# ShematicPCB.net
KiCad netlist of a schematic drawn in EAGLE
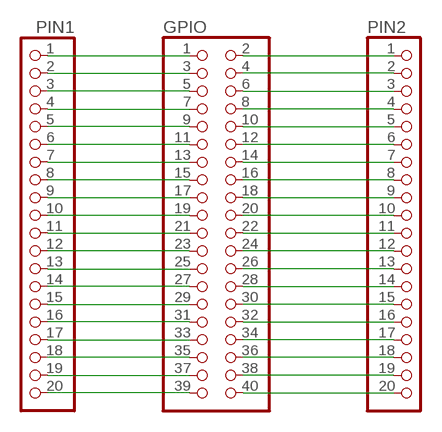
[diagram p0: schematic, sheet 1]

(export (version "E")
  (design (tool "Eeschema 10.0.6"))
  (components
    (comp (ref "GPIO")
      (value "PINHD-2X20")
      (footprint "eagle-import:2X20")
      (libsource (lib "eagle-import") (part "PINHD-2X20"))
    )
    (comp (ref "PIN1")
      (value "PINHD-1X20")
      (footprint "eagle-import:1X20")
      (libsource (lib "eagle-import") (part "PINHD-1X20"))
    )
    (comp (ref "PIN2")
      (value "PINHD-1X20")
      (footprint "eagle-import:1X20")
      (libsource (lib "eagle-import") (part "PINHD-1X20"))
    )
  )
  (nets
    (net (code "1") (name "Net-(GPIO-Pad1)") (class "Default")
      (node (ref "GPIO") (pin "1") (pinfunction "1_1") (pintype "passive"))
      (node (ref "PIN1") (pin "1") (pinfunction "1_1") (pintype "passive"))
    )
    (net (code "2") (name "Net-(GPIO-Pad2)") (class "Default")
      (node (ref "GPIO") (pin "2") (pinfunction "2_2") (pintype "passive"))
      (node (ref "PIN2") (pin "1") (pinfunction "1_1") (pintype "passive"))
    )
    (net (code "3") (name "Net-(GPIO-Pad3)") (class "Default")
      (node (ref "GPIO") (pin "3") (pinfunction "3_3") (pintype "passive"))
      (node (ref "PIN1") (pin "2") (pinfunction "2_2") (pintype "passive"))
    )
    (net (code "4") (name "Net-(GPIO-Pad4)") (class "Default")
      (node (ref "GPIO") (pin "4") (pinfunction "4_4") (pintype "passive"))
      (node (ref "PIN2") (pin "2") (pinfunction "2_2") (pintype "passive"))
    )
    (net (code "5") (name "Net-(GPIO-Pad5)") (class "Default")
      (node (ref "GPIO") (pin "5") (pinfunction "5_5") (pintype "passive"))
      (node (ref "PIN1") (pin "3") (pinfunction "3_3") (pintype "passive"))
    )
    (net (code "6") (name "Net-(GPIO-Pad6)") (class "Default")
      (node (ref "GPIO") (pin "6") (pinfunction "6_6") (pintype "passive"))
      (node (ref "PIN2") (pin "3") (pinfunction "3_3") (pintype "passive"))
    )
    (net (code "7") (name "Net-(GPIO-Pad7)") (class "Default")
      (node (ref "GPIO") (pin "7") (pinfunction "7_7") (pintype "passive"))
      (node (ref "PIN1") (pin "4") (pinfunction "4_4") (pintype "passive"))
    )
    (net (code "8") (name "Net-(GPIO-Pad8)") (class "Default")
      (node (ref "GPIO") (pin "8") (pinfunction "8_8") (pintype "passive"))
      (node (ref "PIN2") (pin "4") (pinfunction "4_4") (pintype "passive"))
    )
    (net (code "9") (name "Net-(GPIO-Pad9)") (class "Default")
      (node (ref "GPIO") (pin "9") (pinfunction "9_9") (pintype "passive"))
      (node (ref "PIN1") (pin "5") (pinfunction "5_5") (pintype "passive"))
    )
    (net (code "10") (name "Net-(GPIO-Pad10)") (class "Default")
      (node (ref "GPIO") (pin "10") (pinfunction "10_10") (pintype "passive"))
      (node (ref "PIN2") (pin "5") (pinfunction "5_5") (pintype "passive"))
    )
    (net (code "11") (name "Net-(GPIO-Pad11)") (class "Default")
      (node (ref "GPIO") (pin "11") (pinfunction "11_11") (pintype "passive"))
      (node (ref "PIN1") (pin "6") (pinfunction "6_6") (pintype "passive"))
    )
    (net (code "12") (name "Net-(GPIO-Pad12)") (class "Default")
      (node (ref "GPIO") (pin "12") (pinfunction "12_12") (pintype "passive"))
      (node (ref "PIN2") (pin "6") (pinfunction "6_6") (pintype "passive"))
    )
    (net (code "13") (name "Net-(GPIO-Pad13)") (class "Default")
      (node (ref "GPIO") (pin "13") (pinfunction "13_13") (pintype "passive"))
      (node (ref "PIN1") (pin "7") (pinfunction "7_7") (pintype "passive"))
    )
    (net (code "14") (name "Net-(GPIO-Pad14)") (class "Default")
      (node (ref "GPIO") (pin "14") (pinfunction "14_14") (pintype "passive"))
      (node (ref "PIN2") (pin "7") (pinfunction "7_7") (pintype "passive"))
    )
    (net (code "15") (name "Net-(GPIO-Pad15)") (class "Default")
      (node (ref "GPIO") (pin "15") (pinfunction "15_15") (pintype "passive"))
      (node (ref "PIN1") (pin "8") (pinfunction "8_8") (pintype "passive"))
    )
    (net (code "16") (name "Net-(GPIO-Pad16)") (class "Default")
      (node (ref "GPIO") (pin "16") (pinfunction "16_16") (pintype "passive"))
      (node (ref "PIN2") (pin "8") (pinfunction "8_8") (pintype "passive"))
    )
    (net (code "17") (name "Net-(GPIO-Pad17)") (class "Default")
      (node (ref "GPIO") (pin "17") (pinfunction "17_17") (pintype "passive"))
      (node (ref "PIN1") (pin "9") (pinfunction "9_9") (pintype "passive"))
    )
    (net (code "18") (name "Net-(GPIO-Pad18)") (class "Default")
      (node (ref "GPIO") (pin "18") (pinfunction "18_18") (pintype "passive"))
      (node (ref "PIN2") (pin "9") (pinfunction "9_9") (pintype "passive"))
    )
    (net (code "19") (name "Net-(GPIO-Pad19)") (class "Default")
      (node (ref "GPIO") (pin "19") (pinfunction "19_19") (pintype "passive"))
      (node (ref "PIN1") (pin "10") (pinfunction "10_10") (pintype "passive"))
    )
    (net (code "20") (name "Net-(GPIO-Pad20)") (class "Default")
      (node (ref "GPIO") (pin "20") (pinfunction "20_20") (pintype "passive"))
      (node (ref "PIN2") (pin "10") (pinfunction "10_10") (pintype "passive"))
    )
    (net (code "21") (name "Net-(GPIO-Pad21)") (class "Default")
      (node (ref "GPIO") (pin "21") (pinfunction "21_21") (pintype "passive"))
      (node (ref "PIN1") (pin "11") (pinfunction "11_11") (pintype "passive"))
    )
    (net (code "22") (name "Net-(GPIO-Pad22)") (class "Default")
      (node (ref "GPIO") (pin "22") (pinfunction "22_22") (pintype "passive"))
      (node (ref "PIN2") (pin "11") (pinfunction "11_11") (pintype "passive"))
    )
    (net (code "23") (name "Net-(GPIO-Pad23)") (class "Default")
      (node (ref "GPIO") (pin "23") (pinfunction "23_23") (pintype "passive"))
      (node (ref "PIN1") (pin "12") (pinfunction "12_12") (pintype "passive"))
    )
    (net (code "24") (name "Net-(GPIO-Pad24)") (class "Default")
      (node (ref "GPIO") (pin "24") (pinfunction "24_24") (pintype "passive"))
      (node (ref "PIN2") (pin "12") (pinfunction "12_12") (pintype "passive"))
    )
    (net (code "25") (name "Net-(GPIO-Pad25)") (class "Default")
      (node (ref "GPIO") (pin "25") (pinfunction "25_25") (pintype "passive"))
      (node (ref "PIN1") (pin "13") (pinfunction "13_13") (pintype "passive"))
    )
    (net (code "26") (name "Net-(GPIO-Pad26)") (class "Default")
      (node (ref "GPIO") (pin "26") (pinfunction "26_26") (pintype "passive"))
      (node (ref "PIN2") (pin "13") (pinfunction "13_13") (pintype "passive"))
    )
    (net (code "27") (name "Net-(GPIO-Pad27)") (class "Default")
      (node (ref "GPIO") (pin "27") (pinfunction "27_27") (pintype "passive"))
      (node (ref "PIN1") (pin "14") (pinfunction "14_14") (pintype "passive"))
    )
    (net (code "28") (name "Net-(GPIO-Pad28)") (class "Default")
      (node (ref "GPIO") (pin "28") (pinfunction "28_28") (pintype "passive"))
      (node (ref "PIN2") (pin "14") (pinfunction "14_14") (pintype "passive"))
    )
    (net (code "29") (name "Net-(GPIO-Pad29)") (class "Default")
      (node (ref "GPIO") (pin "29") (pinfunction "29_29") (pintype "passive"))
      (node (ref "PIN1") (pin "15") (pinfunction "15_15") (pintype "passive"))
    )
    (net (code "30") (name "Net-(GPIO-Pad30)") (class "Default")
      (node (ref "GPIO") (pin "30") (pinfunction "30_30") (pintype "passive"))
      (node (ref "PIN2") (pin "15") (pinfunction "15_15") (pintype "passive"))
    )
    (net (code "31") (name "Net-(GPIO-Pad31)") (class "Default")
      (node (ref "GPIO") (pin "31") (pinfunction "31_31") (pintype "passive"))
      (node (ref "PIN1") (pin "16") (pinfunction "16_16") (pintype "passive"))
    )
    (net (code "32") (name "Net-(GPIO-Pad32)") (class "Default")
      (node (ref "GPIO") (pin "32") (pinfunction "32_32") (pintype "passive"))
      (node (ref "PIN2") (pin "16") (pinfunction "16_16") (pintype "passive"))
    )
    (net (code "33") (name "Net-(GPIO-Pad33)") (class "Default")
      (node (ref "GPIO") (pin "33") (pinfunction "33_33") (pintype "passive"))
      (node (ref "PIN1") (pin "17") (pinfunction "17_17") (pintype "passive"))
    )
    (net (code "34") (name "Net-(GPIO-Pad34)") (class "Default")
      (node (ref "GPIO") (pin "34") (pinfunction "34_34") (pintype "passive"))
      (node (ref "PIN2") (pin "17") (pinfunction "17_17") (pintype "passive"))
    )
    (net (code "35") (name "Net-(GPIO-Pad35)") (class "Default")
      (node (ref "GPIO") (pin "35") (pinfunction "35_35") (pintype "passive"))
      (node (ref "PIN1") (pin "18") (pinfunction "18_18") (pintype "passive"))
    )
    (net (code "36") (name "Net-(GPIO-Pad36)") (class "Default")
      (node (ref "GPIO") (pin "36") (pinfunction "36_36") (pintype "passive"))
      (node (ref "PIN2") (pin "18") (pinfunction "18_18") (pintype "passive"))
    )
    (net (code "37") (name "Net-(GPIO-Pad37)") (class "Default")
      (node (ref "GPIO") (pin "37") (pinfunction "37_37") (pintype "passive"))
      (node (ref "PIN1") (pin "19") (pinfunction "19_19") (pintype "passive"))
    )
    (net (code "38") (name "Net-(GPIO-Pad38)") (class "Default")
      (node (ref "GPIO") (pin "38") (pinfunction "38_38") (pintype "passive"))
      (node (ref "PIN2") (pin "19") (pinfunction "19_19") (pintype "passive"))
    )
    (net (code "39") (name "Net-(GPIO-Pad39)") (class "Default")
      (node (ref "GPIO") (pin "39") (pinfunction "39_39") (pintype "passive"))
      (node (ref "PIN1") (pin "20") (pinfunction "20_20") (pintype "passive"))
    )
    (net (code "40") (name "Net-(GPIO-Pad40)") (class "Default")
      (node (ref "GPIO") (pin "40") (pinfunction "40_40") (pintype "passive"))
      (node (ref "PIN2") (pin "20") (pinfunction "20_20") (pintype "passive"))
    )
  )
)
